# astronaut_interface2.net
KiCad netlist of a schematic drawn in EAGLE
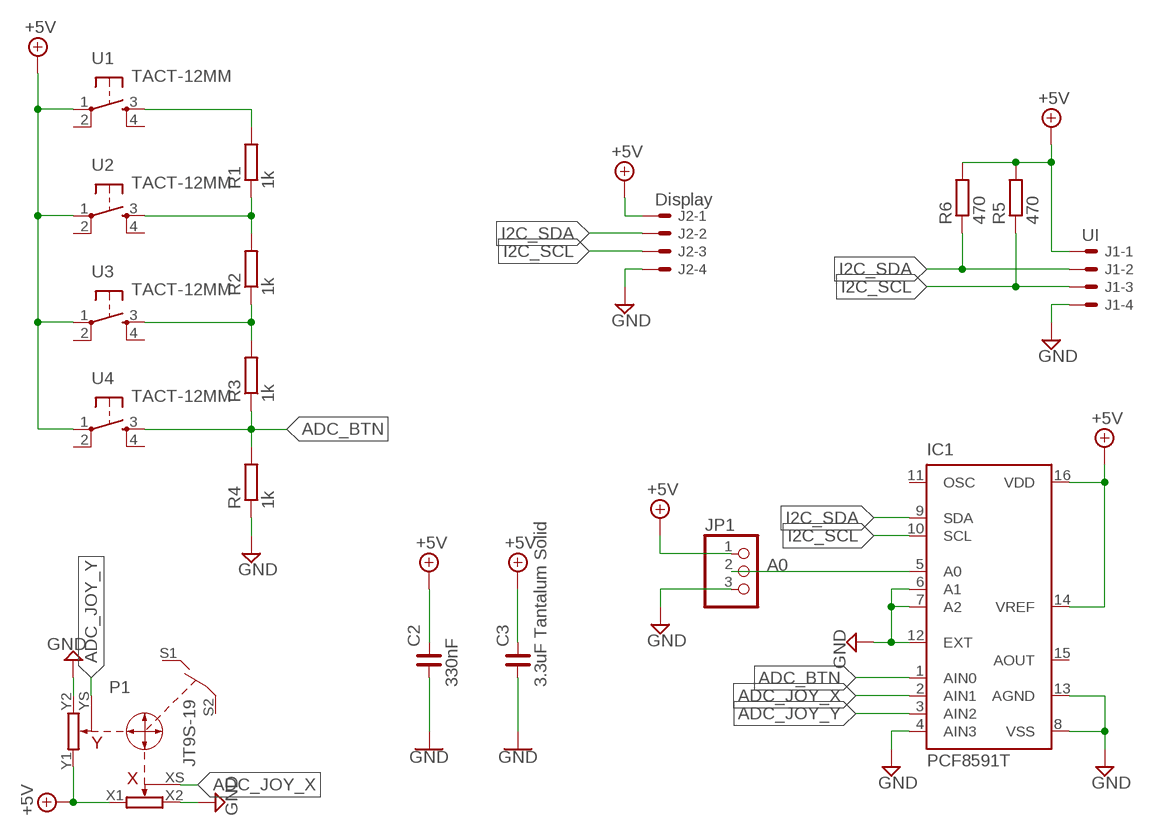
[diagram p0: schematic, sheet 1]

(export (version "E")
  (design (tool "Eeschema 10.0.6"))
  (components
    (comp (ref "C2")
      (value "330nF")
      (footprint "eagle-import:C0805")
      (libsource (lib "eagle-import") (part "C_0805"))
    )
    (comp (ref "C3")
      (value "3.3uF Tantalum Solid")
      (footprint "eagle-import:C1206")
      (libsource (lib "eagle-import") (part "C_1206"))
    )
    (comp (ref "IC1")
      (value "PCF8591T")
      (footprint "eagle-import:SO16W")
      (fields (field (name "MPN") "PCF8591T/2,512"))
      (libsource (lib "eagle-import") (part "PCF8591T"))
    )
    (comp (ref "J1")
      (value "UI")
      (footprint "eagle-import:7395-04")
      (libsource (lib "eagle-import") (part "22-?-0405-7048"))
    )
    (comp (ref "J2")
      (value "Display")
      (footprint "eagle-import:7395-04")
      (libsource (lib "eagle-import") (part "22-?-0405-7048"))
    )
    (comp (ref "JP1")
      (value "PINHD-1X3")
      (footprint "eagle-import:1X03")
      (libsource (lib "eagle-import") (part "PINHD-1X3"))
    )
    (comp (ref "P1")
      (value "JT9S-19")
      (footprint "eagle-import:JT9S-1P")
      (libsource (lib "eagle-import") (part "JT9S-19"))
    )
    (comp (ref "R1")
      (value "1k")
      (footprint "eagle-import:R0805")
      (libsource (lib "eagle-import") (part "R-EU_R0805"))
    )
    (comp (ref "R2")
      (value "1k")
      (footprint "eagle-import:R0805")
      (libsource (lib "eagle-import") (part "R-EU_R0805"))
    )
    (comp (ref "R3")
      (value "1k")
      (footprint "eagle-import:R0805")
      (libsource (lib "eagle-import") (part "R-EU_R0805"))
    )
    (comp (ref "R4")
      (value "1k")
      (footprint "eagle-import:R0805")
      (libsource (lib "eagle-import") (part "R-EU_R0805"))
    )
    (comp (ref "R5")
      (value "470")
      (footprint "eagle-import:M0805")
      (libsource (lib "eagle-import") (part "resistor_R-EU_M0805"))
    )
    (comp (ref "R6")
      (value "470")
      (footprint "eagle-import:M0805")
      (libsource (lib "eagle-import") (part "resistor_R-EU_M0805"))
    )
    (comp (ref "U1")
      (value "TACT-12MM")
      (footprint "eagle-import:TACT-12_THT")
      (libsource (lib "eagle-import") (part "TACT-12MM"))
    )
    (comp (ref "U2")
      (value "TACT-12MM")
      (footprint "eagle-import:TACT-12_THT")
      (libsource (lib "eagle-import") (part "TACT-12MM"))
    )
    (comp (ref "U3")
      (value "TACT-12MM")
      (footprint "eagle-import:TACT-12_THT")
      (libsource (lib "eagle-import") (part "TACT-12MM"))
    )
    (comp (ref "U4")
      (value "TACT-12MM")
      (footprint "eagle-import:TACT-12_THT")
      (libsource (lib "eagle-import") (part "TACT-12MM"))
    )
  )
  (nets
    (net (code "1") (name "+5V") (class "Default")
      (node (ref "C2") (pin "2") (pinfunction "2_2") (pintype "passive"))
      (node (ref "C3") (pin "2") (pinfunction "2_2") (pintype "passive"))
      (node (ref "IC1") (pin "14") (pinfunction "VREF_14") (pintype "input"))
      (node (ref "IC1") (pin "16") (pinfunction "VDD_16") (pintype "power_in"))
      (node (ref "J1") (pin "1") (pinfunction "S_1") (pintype "passive"))
      (node (ref "J2") (pin "1") (pinfunction "S_1") (pintype "passive"))
      (node (ref "JP1") (pin "1") (pinfunction "1_1") (pintype "passive"))
      (node (ref "P1") (pin "X1") (pinfunction "X1_X1") (pintype "passive"))
      (node (ref "P1") (pin "Y1") (pinfunction "Y1_Y1") (pintype "passive"))
      (node (ref "R5") (pin "2") (pinfunction "2_2") (pintype "passive"))
      (node (ref "R6") (pin "2") (pinfunction "2_2") (pintype "passive"))
      (node (ref "U1") (pin "1") (pinfunction "1_1") (pintype "passive"))
      (node (ref "U2") (pin "1") (pinfunction "1_1") (pintype "passive"))
      (node (ref "U3") (pin "1") (pinfunction "1_1") (pintype "passive"))
      (node (ref "U4") (pin "1") (pinfunction "1_1") (pintype "passive"))
    )
    (net (code "2") (name "/A0") (class "Default")
      (node (ref "IC1") (pin "5") (pinfunction "A0_5") (pintype "input"))
      (node (ref "JP1") (pin "2") (pinfunction "2_2") (pintype "passive"))
    )
    (net (code "3") (name "ADC_BTN") (class "Default")
      (node (ref "IC1") (pin "1") (pinfunction "AIN0_1") (pintype "input"))
      (node (ref "R3") (pin "1") (pinfunction "1_1") (pintype "passive"))
      (node (ref "R4") (pin "2") (pinfunction "2_2") (pintype "passive"))
      (node (ref "U4") (pin "3") (pinfunction "3_3") (pintype "passive"))
    )
    (net (code "4") (name "ADC_JOY_X") (class "Default")
      (node (ref "IC1") (pin "2") (pinfunction "AIN1_2") (pintype "input"))
      (node (ref "P1") (pin "XS") (pinfunction "XS_XS") (pintype "passive"))
    )
    (net (code "5") (name "ADC_JOY_Y") (class "Default")
      (node (ref "IC1") (pin "3") (pinfunction "AIN2_3") (pintype "input"))
      (node (ref "P1") (pin "YS") (pinfunction "YS_YS") (pintype "passive"))
    )
    (net (code "6") (name "GND") (class "Default")
      (node (ref "C2") (pin "1") (pinfunction "1_1") (pintype "passive"))
      (node (ref "C3") (pin "1") (pinfunction "1_1") (pintype "passive"))
      (node (ref "IC1") (pin "12") (pinfunction "EXT_12") (pintype "input"))
      (node (ref "IC1") (pin "13") (pinfunction "AGND_13") (pintype "power_in"))
      (node (ref "IC1") (pin "4") (pinfunction "AIN3_4") (pintype "input"))
      (node (ref "IC1") (pin "6") (pinfunction "A1_6") (pintype "input"))
      (node (ref "IC1") (pin "7") (pinfunction "A2_7") (pintype "input"))
      (node (ref "IC1") (pin "8") (pinfunction "VSS_8") (pintype "power_in"))
      (node (ref "J1") (pin "4") (pinfunction "S_4") (pintype "passive"))
      (node (ref "J2") (pin "4") (pinfunction "S_4") (pintype "passive"))
      (node (ref "JP1") (pin "3") (pinfunction "3_3") (pintype "passive"))
      (node (ref "P1") (pin "X2") (pinfunction "X2_X2") (pintype "passive"))
      (node (ref "P1") (pin "Y2") (pinfunction "Y2_Y2") (pintype "passive"))
      (node (ref "R4") (pin "1") (pinfunction "1_1") (pintype "passive"))
    )
    (net (code "7") (name "I2C_SCL") (class "Default")
      (node (ref "IC1") (pin "10") (pinfunction "SCL_10") (pintype "input"))
      (node (ref "J1") (pin "3") (pinfunction "S_3") (pintype "passive"))
      (node (ref "J2") (pin "3") (pinfunction "S_3") (pintype "passive"))
      (node (ref "R5") (pin "1") (pinfunction "1_1") (pintype "passive"))
    )
    (net (code "8") (name "I2C_SDA") (class "Default")
      (node (ref "IC1") (pin "9") (pinfunction "SDA_9") (pintype "bidirectional"))
      (node (ref "J1") (pin "2") (pinfunction "S_2") (pintype "passive"))
      (node (ref "J2") (pin "2") (pinfunction "S_2") (pintype "passive"))
      (node (ref "R6") (pin "1") (pinfunction "1_1") (pintype "passive"))
    )
    (net (code "9") (name "Net-(R1-Pad1)") (class "Default")
      (node (ref "R1") (pin "1") (pinfunction "1_1") (pintype "passive"))
      (node (ref "R2") (pin "2") (pinfunction "2_2") (pintype "passive"))
      (node (ref "U2") (pin "3") (pinfunction "3_3") (pintype "passive"))
    )
    (net (code "10") (name "Net-(R1-Pad2)") (class "Default")
      (node (ref "R1") (pin "2") (pinfunction "2_2") (pintype "passive"))
      (node (ref "U1") (pin "3") (pinfunction "3_3") (pintype "passive"))
    )
    (net (code "11") (name "Net-(R2-Pad1)") (class "Default")
      (node (ref "R2") (pin "1") (pinfunction "1_1") (pintype "passive"))
      (node (ref "R3") (pin "2") (pinfunction "2_2") (pintype "passive"))
      (node (ref "U3") (pin "3") (pinfunction "3_3") (pintype "passive"))
    )
    (net (code "12") (name "unconnected-(IC1-AOUT-Pad15)") (class "Default")
      (node (ref "IC1") (pin "15") (pinfunction "AOUT_15") (pintype "output"))
    )
    (net (code "13") (name "unconnected-(IC1-OSC-Pad11)") (class "Default")
      (node (ref "IC1") (pin "11") (pinfunction "OSC_11") (pintype "input"))
    )
    (net (code "14") (name "unconnected-(P1-PadS1)") (class "Default")
      (node (ref "P1") (pin "S1") (pinfunction "S1_S1") (pintype "passive"))
    )
    (net (code "15") (name "unconnected-(P1-PadS2)") (class "Default")
      (node (ref "P1") (pin "S2") (pinfunction "S2_S2") (pintype "passive"))
    )
    (net (code "16") (name "unconnected-(U1-Pad2)") (class "Default")
      (node (ref "U1") (pin "2") (pinfunction "2_2") (pintype "passive"))
    )
    (net (code "17") (name "unconnected-(U1-Pad4)") (class "Default")
      (node (ref "U1") (pin "4") (pinfunction "4_4") (pintype "passive"))
    )
    (net (code "18") (name "unconnected-(U2-Pad2)") (class "Default")
      (node (ref "U2") (pin "2") (pinfunction "2_2") (pintype "passive"))
    )
    (net (code "19") (name "unconnected-(U2-Pad4)") (class "Default")
      (node (ref "U2") (pin "4") (pinfunction "4_4") (pintype "passive"))
    )
    (net (code "20") (name "unconnected-(U3-Pad2)") (class "Default")
      (node (ref "U3") (pin "2") (pinfunction "2_2") (pintype "passive"))
    )
    (net (code "21") (name "unconnected-(U3-Pad4)") (class "Default")
      (node (ref "U3") (pin "4") (pinfunction "4_4") (pintype "passive"))
    )
    (net (code "22") (name "unconnected-(U4-Pad2)") (class "Default")
      (node (ref "U4") (pin "2") (pinfunction "2_2") (pintype "passive"))
    )
    (net (code "23") (name "unconnected-(U4-Pad4)") (class "Default")
      (node (ref "U4") (pin "4") (pinfunction "4_4") (pintype "passive"))
    )
  )
)
